# Single_Socket_NoPower.net
KiCad netlist of a schematic drawn in EAGLE
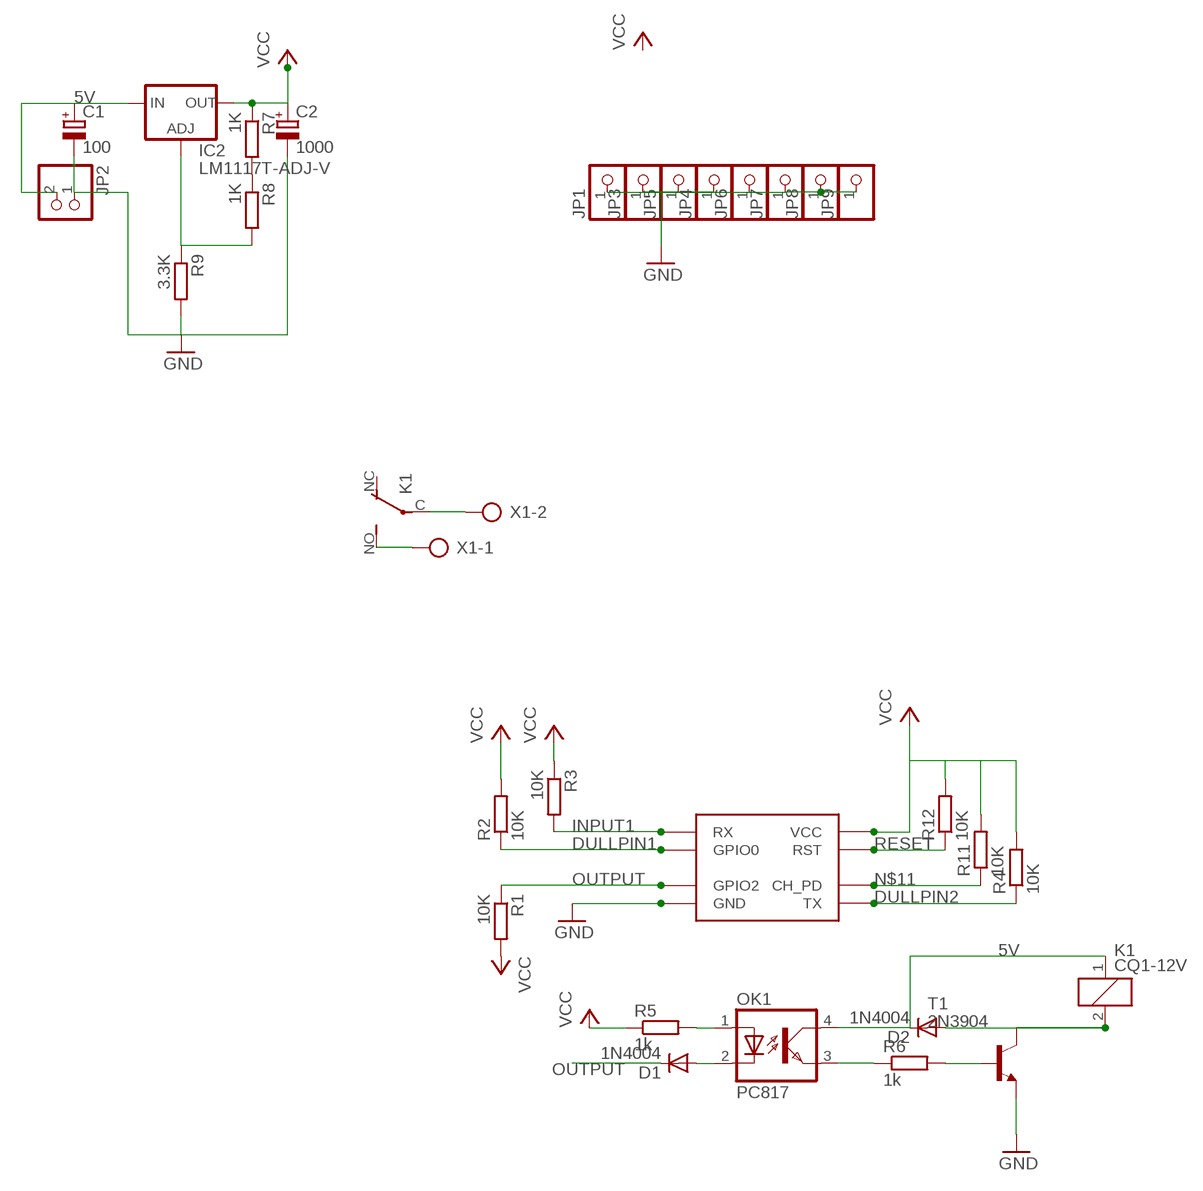
[diagram p0: schematic, sheet 1]

(export (version "E")
  (design (tool "Eeschema 10.0.6"))
  (components
    (comp (ref "C1")
      (value "100")
      (footprint "eagle-import:E5-10,5")
      (libsource (lib "eagle-import") (part "CPOL-EUE5-10.5"))
    )
    (comp (ref "C2")
      (value "1000")
      (footprint "eagle-import:E5-10,5")
      (libsource (lib "eagle-import") (part "CPOL-EUE5-10.5"))
    )
    (comp (ref "D1")
      (value "1N4004")
      (footprint "eagle-import:DO41-10")
      (libsource (lib "eagle-import") (part "1N4004"))
    )
    (comp (ref "D2")
      (value "1N4004")
      (footprint "eagle-import:DO41-10")
      (libsource (lib "eagle-import") (part "1N4004"))
    )
    (comp (ref "IC2")
      (value "LM1117T-ADJ-V")
      (footprint "eagle-import:TO220V")
      (libsource (lib "eagle-import") (part "LM1117T-ADJ-V"))
    )
    (comp (ref "JP1")
      (value "PINHD-1X1")
      (footprint "eagle-import:1X01")
      (libsource (lib "eagle-import") (part "PINHD-1X1"))
    )
    (comp (ref "JP2")
      (value "PINHD-1X2")
      (footprint "eagle-import:1X02")
      (libsource (lib "eagle-import") (part "PINHD-1X2"))
    )
    (comp (ref "JP3")
      (value "PINHD-1X1")
      (footprint "eagle-import:1X01")
      (libsource (lib "eagle-import") (part "PINHD-1X1"))
    )
    (comp (ref "JP4")
      (value "PINHD-1X1")
      (footprint "eagle-import:1X01")
      (libsource (lib "eagle-import") (part "PINHD-1X1"))
    )
    (comp (ref "JP5")
      (value "PINHD-1X1")
      (footprint "eagle-import:1X01")
      (libsource (lib "eagle-import") (part "PINHD-1X1"))
    )
    (comp (ref "JP6")
      (value "PINHD-1X1")
      (footprint "eagle-import:1X01")
      (libsource (lib "eagle-import") (part "PINHD-1X1"))
    )
    (comp (ref "JP7")
      (value "PINHD-1X1")
      (footprint "eagle-import:1X01")
      (libsource (lib "eagle-import") (part "PINHD-1X1"))
    )
    (comp (ref "JP8")
      (value "PINHD-1X1")
      (footprint "eagle-import:1X01")
      (libsource (lib "eagle-import") (part "PINHD-1X1"))
    )
    (comp (ref "JP9")
      (value "PINHD-1X1")
      (footprint "eagle-import:1X01")
      (libsource (lib "eagle-import") (part "PINHD-1X1"))
    )
    (comp (ref "K1")
      (value "CQ1-12V")
      (footprint "eagle-import:CQ1")
      (libsource (lib "eagle-import") (part "CQ1-12V"))
    )
    (comp (ref "OK1")
      (value "PC817")
      (footprint "eagle-import:DIL04")
      (fields (field (name "MPN") "PC817X4J000F"))
      (libsource (lib "eagle-import") (part "PC817"))
    )
    (comp (ref "R1")
      (value "10K")
      (footprint "eagle-import:0207_10")
      (libsource (lib "eagle-import") (part "R-EU_0207/10"))
    )
    (comp (ref "R2")
      (value "10K")
      (footprint "eagle-import:0207_10")
      (libsource (lib "eagle-import") (part "R-EU_0207/10"))
    )
    (comp (ref "R3")
      (value "10K")
      (footprint "eagle-import:0207_10")
      (libsource (lib "eagle-import") (part "R-EU_0207/10"))
    )
    (comp (ref "R4")
      (value "10K")
      (footprint "eagle-import:0207_10")
      (libsource (lib "eagle-import") (part "R-EU_0207/10"))
    )
    (comp (ref "R5")
      (value "1k")
      (footprint "eagle-import:0207_10")
      (libsource (lib "eagle-import") (part "R-EU_0207/10"))
    )
    (comp (ref "R6")
      (value "1k")
      (footprint "eagle-import:0207_10")
      (libsource (lib "eagle-import") (part "R-EU_0207/10"))
    )
    (comp (ref "R7")
      (value "1K")
      (footprint "eagle-import:0207_10")
      (libsource (lib "eagle-import") (part "R-EU_0207/10"))
    )
    (comp (ref "R8")
      (value "1K")
      (footprint "eagle-import:0207_10")
      (libsource (lib "eagle-import") (part "R-EU_0207/10"))
    )
    (comp (ref "R9")
      (value "3.3K")
      (footprint "eagle-import:0207_10")
      (libsource (lib "eagle-import") (part "R-EU_0207/10"))
    )
    (comp (ref "R11")
      (value "10K")
      (footprint "eagle-import:0207_10")
      (libsource (lib "eagle-import") (part "R-EU_0207/10"))
    )
    (comp (ref "R12")
      (value "10K")
      (footprint "eagle-import:0207_10")
      (libsource (lib "eagle-import") (part "R-EU_0207/10"))
    )
    (comp (ref "T1")
      (value "2N3904")
      (footprint "eagle-import:TO92")
      (libsource (lib "eagle-import") (part "2N3904"))
    )
    (comp (ref "U$2")
      (value "ESP8266")
      (footprint "eagle-import:ESP8266")
      (libsource (lib "eagle-import") (part "ESP8266"))
    )
    (comp (ref "X1")
      (value "AK500/2-H")
      (footprint "eagle-import:AK500_2-H")
      (libsource (lib "eagle-import") (part "AK500/2-H"))
    )
  )
  (nets
    (net (code "1") (name "/5V") (class "Default")
      (node (ref "C1") (pin "+") (pinfunction "+_+") (pintype "passive"))
      (node (ref "D2") (pin "C") (pinfunction "C_C") (pintype "passive"))
      (node (ref "IC2") (pin "3") (pinfunction "IN_3") (pintype "input"))
      (node (ref "JP2") (pin "2") (pinfunction "2_2") (pintype "passive"))
      (node (ref "K1") (pin "1") (pinfunction "1_1") (pintype "passive"))
      (node (ref "OK1") (pin "4") (pinfunction "COL_4") (pintype "passive"))
    )
    (net (code "2") (name "/DULLPIN1") (class "Default")
      (node (ref "R2") (pin "1") (pinfunction "1_1") (pintype "passive"))
      (node (ref "U$2") (pin "GPIO0") (pinfunction "GPIO0_GPIO0") (pintype "bidirectional"))
    )
    (net (code "3") (name "/DULLPIN2") (class "Default")
      (node (ref "R4") (pin "1") (pinfunction "1_1") (pintype "passive"))
      (node (ref "U$2") (pin "TX") (pinfunction "TX_TX") (pintype "bidirectional"))
    )
    (net (code "4") (name "/INPUT1") (class "Default")
      (node (ref "R3") (pin "2") (pinfunction "2_2") (pintype "passive"))
      (node (ref "U$2") (pin "RX") (pinfunction "RX_RX") (pintype "bidirectional"))
    )
    (net (code "5") (name "/N$11") (class "Default")
      (node (ref "R11") (pin "1") (pinfunction "1_1") (pintype "passive"))
      (node (ref "U$2") (pin "CH_PD") (pinfunction "CH_PD_CH_PD") (pintype "bidirectional"))
    )
    (net (code "6") (name "/OUTPUT") (class "Default")
      (node (ref "D1") (pin "C") (pinfunction "C_C") (pintype "passive"))
      (node (ref "R1") (pin "1") (pinfunction "1_1") (pintype "passive"))
      (node (ref "U$2") (pin "GPIO2") (pinfunction "GPIO2_GPIO2") (pintype "bidirectional"))
    )
    (net (code "7") (name "/RESET") (class "Default")
      (node (ref "R12") (pin "1") (pinfunction "1_1") (pintype "passive"))
      (node (ref "U$2") (pin "RST") (pinfunction "RST_RST") (pintype "bidirectional"))
    )
    (net (code "8") (name "GND") (class "Default")
      (node (ref "C1") (pin "-") (pinfunction "-_-") (pintype "passive"))
      (node (ref "C2") (pin "-") (pinfunction "-_-") (pintype "passive"))
      (node (ref "JP1") (pin "1") (pinfunction "1_1") (pintype "passive"))
      (node (ref "JP2") (pin "1") (pinfunction "1_1") (pintype "passive"))
      (node (ref "JP3") (pin "1") (pinfunction "1_1") (pintype "passive"))
      (node (ref "JP4") (pin "1") (pinfunction "1_1") (pintype "passive"))
      (node (ref "JP5") (pin "1") (pinfunction "1_1") (pintype "passive"))
      (node (ref "JP6") (pin "1") (pinfunction "1_1") (pintype "passive"))
      (node (ref "JP7") (pin "1") (pinfunction "1_1") (pintype "passive"))
      (node (ref "JP8") (pin "1") (pinfunction "1_1") (pintype "passive"))
      (node (ref "JP9") (pin "1") (pinfunction "1_1") (pintype "passive"))
      (node (ref "R9") (pin "2") (pinfunction "2_2") (pintype "passive"))
      (node (ref "T1") (pin "3") (pinfunction "E_3") (pintype "passive"))
      (node (ref "U$2") (pin "GND") (pinfunction "GND_GND") (pintype "bidirectional"))
    )
    (net (code "9") (name "Net-(IC2-ADJ)") (class "Default")
      (node (ref "IC2") (pin "1") (pinfunction "ADJ_1") (pintype "input"))
      (node (ref "R8") (pin "2") (pinfunction "2_2") (pintype "passive"))
      (node (ref "R9") (pin "1") (pinfunction "1_1") (pintype "passive"))
    )
    (net (code "10") (name "Net-(K1B-P)") (class "Default")
      (node (ref "K1") (pin "C") (pinfunction "P_C") (pintype "passive"))
      (node (ref "X1") (pin "2") (pinfunction "KL_2") (pintype "passive"))
    )
    (net (code "11") (name "Net-(K1B-S)") (class "Default")
      (node (ref "K1") (pin "NO") (pinfunction "S_NO") (pintype "passive"))
      (node (ref "X1") (pin "1") (pinfunction "KL_1") (pintype "passive"))
    )
    (net (code "12") (name "Net-(OK1-A)") (class "Default")
      (node (ref "OK1") (pin "1") (pinfunction "A_1") (pintype "passive"))
      (node (ref "R5") (pin "2") (pinfunction "2_2") (pintype "passive"))
    )
    (net (code "13") (name "Net-(OK1-C)") (class "Default")
      (node (ref "D1") (pin "A") (pinfunction "A_A") (pintype "passive"))
      (node (ref "OK1") (pin "2") (pinfunction "C_2") (pintype "passive"))
    )
    (net (code "14") (name "Net-(OK1-EMIT)") (class "Default")
      (node (ref "OK1") (pin "3") (pinfunction "EMIT_3") (pintype "passive"))
      (node (ref "R6") (pin "1") (pinfunction "1_1") (pintype "passive"))
    )
    (net (code "15") (name "Net-(R7-Pad2)") (class "Default")
      (node (ref "R7") (pin "2") (pinfunction "2_2") (pintype "passive"))
      (node (ref "R8") (pin "1") (pinfunction "1_1") (pintype "passive"))
    )
    (net (code "16") (name "Net-(T1-B)") (class "Default")
      (node (ref "R6") (pin "2") (pinfunction "2_2") (pintype "passive"))
      (node (ref "T1") (pin "2") (pinfunction "B_2") (pintype "passive"))
    )
    (net (code "17") (name "Net-(T1-C)") (class "Default")
      (node (ref "D2") (pin "A") (pinfunction "A_A") (pintype "passive"))
      (node (ref "K1") (pin "2") (pinfunction "2_2") (pintype "passive"))
      (node (ref "T1") (pin "1") (pinfunction "C_1") (pintype "passive"))
    )
    (net (code "18") (name "VCC") (class "Default")
      (node (ref "C2") (pin "+") (pinfunction "+_+") (pintype "passive"))
      (node (ref "IC2") (pin "2") (pinfunction "OUT_2") (pintype "passive"))
      (node (ref "R1") (pin "2") (pinfunction "2_2") (pintype "passive"))
      (node (ref "R11") (pin "2") (pinfunction "2_2") (pintype "passive"))
      (node (ref "R12") (pin "2") (pinfunction "2_2") (pintype "passive"))
      (node (ref "R2") (pin "2") (pinfunction "2_2") (pintype "passive"))
      (node (ref "R3") (pin "1") (pinfunction "1_1") (pintype "passive"))
      (node (ref "R4") (pin "2") (pinfunction "2_2") (pintype "passive"))
      (node (ref "R5") (pin "1") (pinfunction "1_1") (pintype "passive"))
      (node (ref "R7") (pin "1") (pinfunction "1_1") (pintype "passive"))
      (node (ref "U$2") (pin "VCC") (pinfunction "VCC_VCC") (pintype "bidirectional"))
    )
    (net (code "19") (name "unconnected-(K1B-O-PadNC)") (class "Default")
      (node (ref "K1") (pin "NC") (pinfunction "O_NC") (pintype "passive"))
    )
  )
)
